# rc2014_16550c.net
KiCad netlist of a schematic drawn in EAGLE
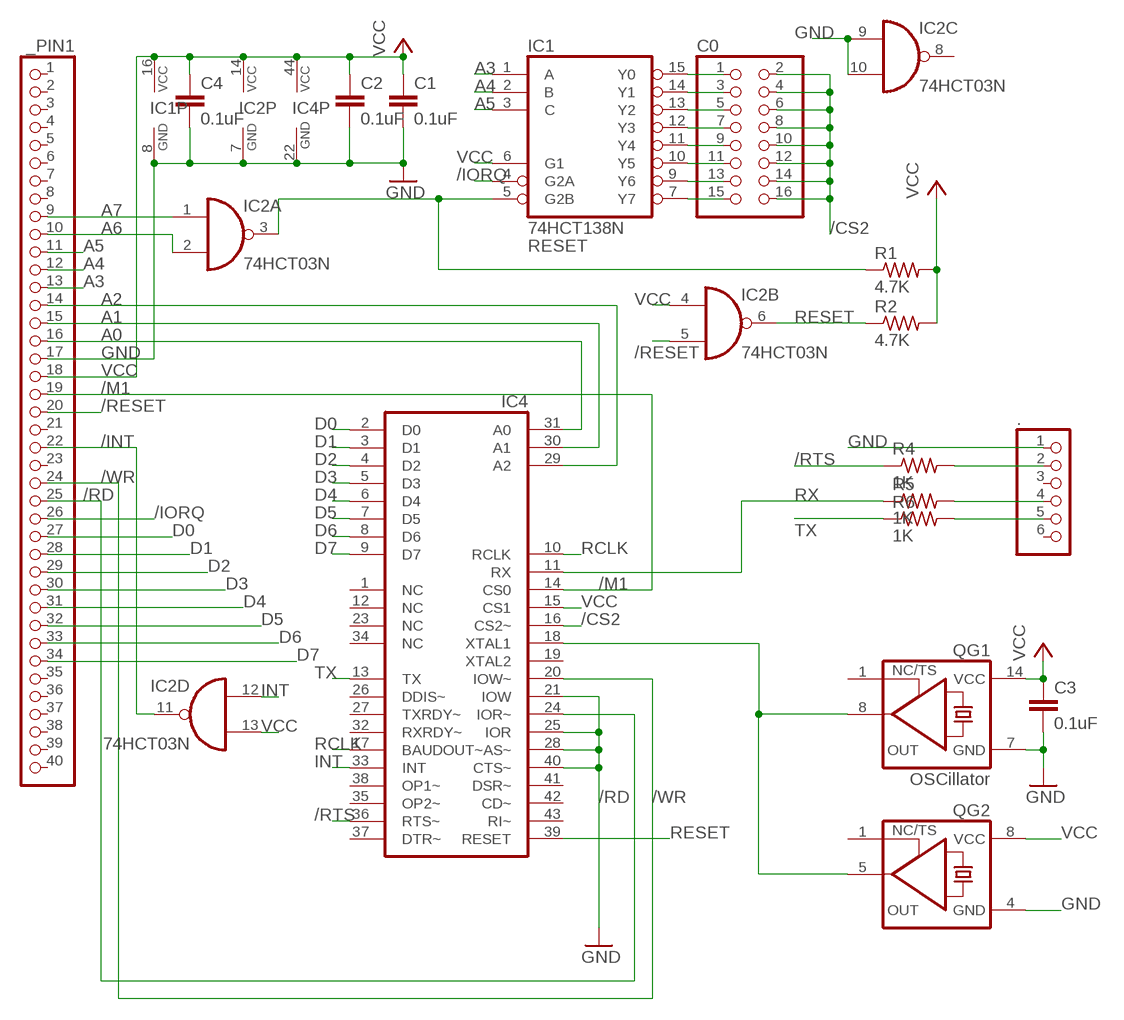
[diagram p0: schematic, sheet 1]

(export (version "E")
  (design (tool "Eeschema 10.0.6"))
  (components
    (comp (ref ".")
      (value "PINHD-1X6")
      (footprint "eagle-import:1X06")
      (libsource (lib "eagle-import") (part "PINHD-1X6"))
    )
    (comp (ref "C0")
      (value "PINHD-2X8")
      (footprint "eagle-import:2X08")
      (libsource (lib "eagle-import") (part "PINHD-2X8"))
    )
    (comp (ref "C1")
      (value "0.1uF")
      (footprint "eagle-import:C050-024X044")
      (libsource (lib "eagle-import") (part "C-EU050-024X044"))
    )
    (comp (ref "C2")
      (value "0.1uF")
      (footprint "eagle-import:C050-024X044")
      (libsource (lib "eagle-import") (part "C-EU050-024X044"))
    )
    (comp (ref "C3")
      (value "0.1uF")
      (footprint "eagle-import:C050-024X044")
      (libsource (lib "eagle-import") (part "C-EU050-024X044"))
    )
    (comp (ref "C4")
      (value "0.1uF")
      (footprint "eagle-import:C050-024X044")
      (libsource (lib "eagle-import") (part "C-EU050-024X044"))
    )
    (comp (ref "IC1")
      (value "74HCT138N")
      (footprint "eagle-import:DIL16")
      (libsource (lib "eagle-import") (part "74138NHCT"))
    )
    (comp (ref "IC2")
      (value "74HCT03N")
      (footprint "eagle-import:DIL14")
      (libsource (lib "eagle-import") (part "7400NHCT"))
    )
    (comp (ref "IC4")
      (value "XR-16C550JSOCKET44")
      (footprint "eagle-import:S44")
      (libsource (lib "eagle-import") (part "XR-16C550JSOCKET44"))
    )
    (comp (ref "QG1")
      (value "OSCillator")
      (footprint "eagle-import:DIL14S")
      (libsource (lib "eagle-import") (part "XO-14"))
    )
    (comp (ref "QG2")
      (value "XO-8")
      (footprint "eagle-import:DIL08S")
      (libsource (lib "eagle-import") (part "XO-8"))
    )
    (comp (ref "R1")
      (value "4.7K")
      (footprint "eagle-import:0207_10")
      (libsource (lib "eagle-import") (part "R-US_0207/10"))
    )
    (comp (ref "R2")
      (value "4.7K")
      (footprint "eagle-import:0207_10")
      (libsource (lib "eagle-import") (part "R-US_0207/10"))
    )
    (comp (ref "R4")
      (value "1K")
      (footprint "eagle-import:0207_10")
      (libsource (lib "eagle-import") (part "R-US_0207/10"))
    )
    (comp (ref "R5")
      (value "1K")
      (footprint "eagle-import:0207_10")
      (libsource (lib "eagle-import") (part "R-US_0207/10"))
    )
    (comp (ref "R6")
      (value "1K")
      (footprint "eagle-import:0207_10")
      (libsource (lib "eagle-import") (part "R-US_0207/10"))
    )
    (comp (ref "_PIN1")
      (value "PINHD-1X40")
      (footprint "eagle-import:1X40")
      (libsource (lib "eagle-import") (part "PINHD-1X40"))
    )
  )
  (nets
    (net (code "1") (name "/A0") (class "Default")
      (node (ref "IC4") (pin "31") (pinfunction "A0_31") (pintype "input"))
      (node (ref "_PIN1") (pin "16") (pinfunction "16_16") (pintype "passive"))
    )
    (net (code "2") (name "/A1") (class "Default")
      (node (ref "IC4") (pin "30") (pinfunction "A1_30") (pintype "input"))
      (node (ref "_PIN1") (pin "15") (pinfunction "15_15") (pintype "passive"))
    )
    (net (code "3") (name "/A2") (class "Default")
      (node (ref "IC4") (pin "29") (pinfunction "A2_29") (pintype "input"))
      (node (ref "_PIN1") (pin "14") (pinfunction "14_14") (pintype "passive"))
    )
    (net (code "4") (name "/A3") (class "Default")
      (node (ref "IC1") (pin "1") (pinfunction "A_1") (pintype "input"))
      (node (ref "_PIN1") (pin "13") (pinfunction "13_13") (pintype "passive"))
    )
    (net (code "5") (name "/A4") (class "Default")
      (node (ref "IC1") (pin "2") (pinfunction "B_2") (pintype "input"))
      (node (ref "_PIN1") (pin "12") (pinfunction "12_12") (pintype "passive"))
    )
    (net (code "6") (name "/A5") (class "Default")
      (node (ref "IC1") (pin "3") (pinfunction "C_3") (pintype "input"))
      (node (ref "_PIN1") (pin "11") (pinfunction "11_11") (pintype "passive"))
    )
    (net (code "7") (name "/A6") (class "Default")
      (node (ref "IC2") (pin "2") (pinfunction "I1_2") (pintype "input"))
      (node (ref "_PIN1") (pin "10") (pinfunction "10_10") (pintype "passive"))
    )
    (net (code "8") (name "/A7") (class "Default")
      (node (ref "IC2") (pin "1") (pinfunction "I0_1") (pintype "input"))
      (node (ref "_PIN1") (pin "9") (pinfunction "9_9") (pintype "passive"))
    )
    (net (code "9") (name "/D0") (class "Default")
      (node (ref "IC4") (pin "2") (pinfunction "D0_2") (pintype "bidirectional"))
      (node (ref "_PIN1") (pin "27") (pinfunction "27_27") (pintype "passive"))
    )
    (net (code "10") (name "/D1") (class "Default")
      (node (ref "IC4") (pin "3") (pinfunction "D1_3") (pintype "bidirectional"))
      (node (ref "_PIN1") (pin "28") (pinfunction "28_28") (pintype "passive"))
    )
    (net (code "11") (name "/D2") (class "Default")
      (node (ref "IC4") (pin "4") (pinfunction "D2_4") (pintype "bidirectional"))
      (node (ref "_PIN1") (pin "29") (pinfunction "29_29") (pintype "passive"))
    )
    (net (code "12") (name "/D3") (class "Default")
      (node (ref "IC4") (pin "5") (pinfunction "D3_5") (pintype "bidirectional"))
      (node (ref "_PIN1") (pin "30") (pinfunction "30_30") (pintype "passive"))
    )
    (net (code "13") (name "/D4") (class "Default")
      (node (ref "IC4") (pin "6") (pinfunction "D4_6") (pintype "bidirectional"))
      (node (ref "_PIN1") (pin "31") (pinfunction "31_31") (pintype "passive"))
    )
    (net (code "14") (name "/D5") (class "Default")
      (node (ref "IC4") (pin "7") (pinfunction "D5_7") (pintype "bidirectional"))
      (node (ref "_PIN1") (pin "32") (pinfunction "32_32") (pintype "passive"))
    )
    (net (code "15") (name "/D6") (class "Default")
      (node (ref "IC4") (pin "8") (pinfunction "D6_8") (pintype "bidirectional"))
      (node (ref "_PIN1") (pin "33") (pinfunction "33_33") (pintype "passive"))
    )
    (net (code "16") (name "/D7") (class "Default")
      (node (ref "IC4") (pin "9") (pinfunction "D7_9") (pintype "bidirectional"))
      (node (ref "_PIN1") (pin "34") (pinfunction "34_34") (pintype "passive"))
    )
    (net (code "17") (name "/INT") (class "Default")
      (node (ref "IC2") (pin "12") (pinfunction "I0_12") (pintype "input"))
      (node (ref "IC4") (pin "33") (pinfunction "INT_33") (pintype "output"))
    )
    (net (code "18") (name "/RCLK") (class "Default")
      (node (ref "IC4") (pin "10") (pinfunction "RCLK_10") (pintype "input"))
      (node (ref "IC4") (pin "17") (pinfunction "BAUDOUT~{}_17") (pintype "output"))
    )
    (net (code "19") (name "/RESET") (class "Default")
      (node (ref "IC2") (pin "6") (pinfunction "O_6") (pintype "output"))
      (node (ref "IC4") (pin "39") (pinfunction "RESET_39") (pintype "input"))
      (node (ref "R2") (pin "1") (pinfunction "1_1") (pintype "passive"))
    )
    (net (code "20") (name "/RX") (class "Default")
      (node (ref "IC4") (pin "11") (pinfunction "RX_11") (pintype "input"))
      (node (ref "R5") (pin "1") (pinfunction "1_1") (pintype "passive"))
    )
    (net (code "21") (name "/TX") (class "Default")
      (node (ref "IC4") (pin "13") (pinfunction "TX_13") (pintype "output"))
      (node (ref "R6") (pin "1") (pinfunction "1_1") (pintype "passive"))
    )
    (net (code "22") (name "/{slash}CS2") (class "Default")
      (node (ref "C0") (pin "10") (pinfunction "10_10") (pintype "passive"))
      (node (ref "C0") (pin "12") (pinfunction "12_12") (pintype "passive"))
      (node (ref "C0") (pin "14") (pinfunction "14_14") (pintype "passive"))
      (node (ref "C0") (pin "16") (pinfunction "16_16") (pintype "passive"))
      (node (ref "C0") (pin "2") (pinfunction "2_2") (pintype "passive"))
      (node (ref "C0") (pin "4") (pinfunction "4_4") (pintype "passive"))
      (node (ref "C0") (pin "6") (pinfunction "6_6") (pintype "passive"))
      (node (ref "C0") (pin "8") (pinfunction "8_8") (pintype "passive"))
      (node (ref "IC4") (pin "16") (pinfunction "CS2~{}_16") (pintype "input"))
    )
    (net (code "23") (name "/{slash}INT") (class "Default")
      (node (ref "IC2") (pin "11") (pinfunction "O_11") (pintype "output"))
      (node (ref "_PIN1") (pin "22") (pinfunction "22_22") (pintype "passive"))
    )
    (net (code "24") (name "/{slash}IORQ") (class "Default")
      (node (ref "IC1") (pin "4") (pinfunction "G2A_4") (pintype "input"))
      (node (ref "_PIN1") (pin "26") (pinfunction "26_26") (pintype "passive"))
    )
    (net (code "25") (name "/{slash}M1") (class "Default")
      (node (ref "IC4") (pin "14") (pinfunction "CS0_14") (pintype "input"))
      (node (ref "_PIN1") (pin "19") (pinfunction "19_19") (pintype "passive"))
    )
    (net (code "26") (name "/{slash}RD") (class "Default")
      (node (ref "IC4") (pin "24") (pinfunction "IOR~{}_24") (pintype "input"))
      (node (ref "_PIN1") (pin "25") (pinfunction "25_25") (pintype "passive"))
    )
    (net (code "27") (name "/{slash}RESET") (class "Default")
      (node (ref "IC2") (pin "5") (pinfunction "I1_5") (pintype "input"))
      (node (ref "_PIN1") (pin "20") (pinfunction "20_20") (pintype "passive"))
    )
    (net (code "28") (name "/{slash}RTS") (class "Default")
      (node (ref "IC4") (pin "36") (pinfunction "RTS~{}_36") (pintype "output"))
      (node (ref "R4") (pin "1") (pinfunction "1_1") (pintype "passive"))
    )
    (net (code "29") (name "/{slash}WR") (class "Default")
      (node (ref "IC4") (pin "20") (pinfunction "IOW~{}_20") (pintype "input"))
      (node (ref "_PIN1") (pin "24") (pinfunction "24_24") (pintype "passive"))
    )
    (net (code "30") (name "GND") (class "Default")
      (node (ref ".") (pin "1") (pinfunction "1_1") (pintype "passive"))
      (node (ref "C1") (pin "2") (pinfunction "2_2") (pintype "passive"))
      (node (ref "C2") (pin "2") (pinfunction "2_2") (pintype "passive"))
      (node (ref "C3") (pin "2") (pinfunction "2_2") (pintype "passive"))
      (node (ref "C4") (pin "2") (pinfunction "2_2") (pintype "passive"))
      (node (ref "IC1") (pin "8") (pinfunction "GND_8") (pintype "power_in"))
      (node (ref "IC2") (pin "10") (pinfunction "I1_10") (pintype "input"))
      (node (ref "IC2") (pin "7") (pinfunction "GND_7") (pintype "power_in"))
      (node (ref "IC2") (pin "9") (pinfunction "I0_9") (pintype "input"))
      (node (ref "IC4") (pin "21") (pinfunction "IOW_21") (pintype "input"))
      (node (ref "IC4") (pin "22") (pinfunction "GND_22") (pintype "power_in"))
      (node (ref "IC4") (pin "25") (pinfunction "IOR_25") (pintype "input"))
      (node (ref "IC4") (pin "28") (pinfunction "AS~{}_28") (pintype "input"))
      (node (ref "IC4") (pin "40") (pinfunction "CTS~{}_40") (pintype "input"))
      (node (ref "QG1") (pin "7") (pinfunction "GND_7") (pintype "power_in"))
      (node (ref "QG2") (pin "4") (pinfunction "GND_4") (pintype "power_in"))
      (node (ref "_PIN1") (pin "17") (pinfunction "17_17") (pintype "passive"))
    )
    (net (code "31") (name "Net-(.-Pad2)") (class "Default")
      (node (ref ".") (pin "2") (pinfunction "2_2") (pintype "passive"))
      (node (ref "R4") (pin "2") (pinfunction "2_2") (pintype "passive"))
    )
    (net (code "32") (name "Net-(.-Pad4)") (class "Default")
      (node (ref ".") (pin "4") (pinfunction "4_4") (pintype "passive"))
      (node (ref "R5") (pin "2") (pinfunction "2_2") (pintype "passive"))
    )
    (net (code "33") (name "Net-(.-Pad5)") (class "Default")
      (node (ref ".") (pin "5") (pinfunction "5_5") (pintype "passive"))
      (node (ref "R6") (pin "2") (pinfunction "2_2") (pintype "passive"))
    )
    (net (code "34") (name "Net-(IC1A-G2B)") (class "Default")
      (node (ref "IC1") (pin "5") (pinfunction "G2B_5") (pintype "input"))
      (node (ref "IC2") (pin "3") (pinfunction "O_3") (pintype "output"))
      (node (ref "R1") (pin "1") (pinfunction "1_1") (pintype "passive"))
    )
    (net (code "35") (name "Net-(IC1A-Y0)") (class "Default")
      (node (ref "C0") (pin "1") (pinfunction "1_1") (pintype "passive"))
      (node (ref "IC1") (pin "15") (pinfunction "Y0_15") (pintype "output"))
    )
    (net (code "36") (name "Net-(IC1A-Y1)") (class "Default")
      (node (ref "C0") (pin "3") (pinfunction "3_3") (pintype "passive"))
      (node (ref "IC1") (pin "14") (pinfunction "Y1_14") (pintype "output"))
    )
    (net (code "37") (name "Net-(IC1A-Y2)") (class "Default")
      (node (ref "C0") (pin "5") (pinfunction "5_5") (pintype "passive"))
      (node (ref "IC1") (pin "13") (pinfunction "Y2_13") (pintype "output"))
    )
    (net (code "38") (name "Net-(IC1A-Y3)") (class "Default")
      (node (ref "C0") (pin "7") (pinfunction "7_7") (pintype "passive"))
      (node (ref "IC1") (pin "12") (pinfunction "Y3_12") (pintype "output"))
    )
    (net (code "39") (name "Net-(IC1A-Y4)") (class "Default")
      (node (ref "C0") (pin "9") (pinfunction "9_9") (pintype "passive"))
      (node (ref "IC1") (pin "11") (pinfunction "Y4_11") (pintype "output"))
    )
    (net (code "40") (name "Net-(IC1A-Y5)") (class "Default")
      (node (ref "C0") (pin "11") (pinfunction "11_11") (pintype "passive"))
      (node (ref "IC1") (pin "10") (pinfunction "Y5_10") (pintype "output"))
    )
    (net (code "41") (name "Net-(IC1A-Y6)") (class "Default")
      (node (ref "C0") (pin "13") (pinfunction "13_13") (pintype "passive"))
      (node (ref "IC1") (pin "9") (pinfunction "Y6_9") (pintype "output"))
    )
    (net (code "42") (name "Net-(IC1A-Y7)") (class "Default")
      (node (ref "C0") (pin "15") (pinfunction "15_15") (pintype "passive"))
      (node (ref "IC1") (pin "7") (pinfunction "Y7_7") (pintype "output"))
    )
    (net (code "43") (name "Net-(IC4A-XTAL1)") (class "Default")
      (node (ref "IC4") (pin "18") (pinfunction "XTAL1_18") (pintype "input"))
      (node (ref "QG1") (pin "8") (pinfunction "OUT_8") (pintype "output"))
      (node (ref "QG2") (pin "5") (pinfunction "OUT_5") (pintype "output"))
    )
    (net (code "44") (name "VCC") (class "Default")
      (node (ref "C1") (pin "1") (pinfunction "1_1") (pintype "passive"))
      (node (ref "C2") (pin "1") (pinfunction "1_1") (pintype "passive"))
      (node (ref "C3") (pin "1") (pinfunction "1_1") (pintype "passive"))
      (node (ref "C4") (pin "1") (pinfunction "1_1") (pintype "passive"))
      (node (ref "IC1") (pin "16") (pinfunction "VCC_16") (pintype "power_in"))
      (node (ref "IC1") (pin "6") (pinfunction "G1_6") (pintype "input"))
      (node (ref "IC2") (pin "13") (pinfunction "I1_13") (pintype "input"))
      (node (ref "IC2") (pin "14") (pinfunction "VCC_14") (pintype "power_in"))
      (node (ref "IC2") (pin "4") (pinfunction "I0_4") (pintype "input"))
      (node (ref "IC4") (pin "15") (pinfunction "CS1_15") (pintype "input"))
      (node (ref "IC4") (pin "44") (pinfunction "VCC_44") (pintype "power_in"))
      (node (ref "QG1") (pin "14") (pinfunction "VCC_14") (pintype "power_in"))
      (node (ref "QG2") (pin "8") (pinfunction "VCC_8") (pintype "power_in"))
      (node (ref "R1") (pin "2") (pinfunction "2_2") (pintype "passive"))
      (node (ref "R2") (pin "2") (pinfunction "2_2") (pintype "passive"))
      (node (ref "_PIN1") (pin "18") (pinfunction "18_18") (pintype "passive"))
    )
    (net (code "45") (name "unconnected-(.-Pad3)") (class "Default")
      (node (ref ".") (pin "3") (pinfunction "3_3") (pintype "passive"))
    )
    (net (code "46") (name "unconnected-(.-Pad6)") (class "Default")
      (node (ref ".") (pin "6") (pinfunction "6_6") (pintype "passive"))
    )
    (net (code "47") (name "unconnected-(IC2C-O-Pad8)") (class "Default")
      (node (ref "IC2") (pin "8") (pinfunction "O_8") (pintype "output"))
    )
    (net (code "48") (name "unconnected-(IC4A-CD~{}-Pad42)") (class "Default")
      (node (ref "IC4") (pin "42") (pinfunction "CD~{}_42") (pintype "input"))
    )
    (net (code "49") (name "unconnected-(IC4A-DDIS~{}-Pad26)") (class "Default")
      (node (ref "IC4") (pin "26") (pinfunction "DDIS~{}_26") (pintype "output"))
    )
    (net (code "50") (name "unconnected-(IC4A-DSR~{}-Pad41)") (class "Default")
      (node (ref "IC4") (pin "41") (pinfunction "DSR~{}_41") (pintype "input"))
    )
    (net (code "51") (name "unconnected-(IC4A-DTR~{}-Pad37)") (class "Default")
      (node (ref "IC4") (pin "37") (pinfunction "DTR~{}_37") (pintype "output"))
    )
    (net (code "52") (name "unconnected-(IC4A-NC-Pad1)") (class "Default")
      (node (ref "IC4") (pin "1") (pinfunction "NC_1") (pintype "no_connect"))
    )
    (net (code "53") (name "unconnected-(IC4A-NC-Pad12)") (class "Default")
      (node (ref "IC4") (pin "12") (pinfunction "NC_12") (pintype "no_connect"))
    )
    (net (code "54") (name "unconnected-(IC4A-NC-Pad23)") (class "Default")
      (node (ref "IC4") (pin "23") (pinfunction "NC_23") (pintype "no_connect"))
    )
    (net (code "55") (name "unconnected-(IC4A-NC-Pad34)") (class "Default")
      (node (ref "IC4") (pin "34") (pinfunction "NC_34") (pintype "no_connect"))
    )
    (net (code "56") (name "unconnected-(IC4A-OP1~{}-Pad38)") (class "Default")
      (node (ref "IC4") (pin "38") (pinfunction "OP1~{}_38") (pintype "output"))
    )
    (net (code "57") (name "unconnected-(IC4A-OP2~{}-Pad35)") (class "Default")
      (node (ref "IC4") (pin "35") (pinfunction "OP2~{}_35") (pintype "output"))
    )
    (net (code "58") (name "unconnected-(IC4A-RI~{}-Pad43)") (class "Default")
      (node (ref "IC4") (pin "43") (pinfunction "RI~{}_43") (pintype "input"))
    )
    (net (code "59") (name "unconnected-(IC4A-RXRDY~{}-Pad32)") (class "Default")
      (node (ref "IC4") (pin "32") (pinfunction "RXRDY~{}_32") (pintype "output"))
    )
    (net (code "60") (name "unconnected-(IC4A-TXRDY~{}-Pad27)") (class "Default")
      (node (ref "IC4") (pin "27") (pinfunction "TXRDY~{}_27") (pintype "output"))
    )
    (net (code "61") (name "unconnected-(IC4A-XTAL2-Pad19)") (class "Default")
      (node (ref "IC4") (pin "19") (pinfunction "XTAL2_19") (pintype "input"))
    )
    (net (code "62") (name "unconnected-(QG1-TS-Pad1)") (class "Default")
      (node (ref "QG1") (pin "1") (pinfunction "TS_1") (pintype "passive"))
    )
    (net (code "63") (name "unconnected-(QG2-TS-Pad1)") (class "Default")
      (node (ref "QG2") (pin "1") (pinfunction "TS_1") (pintype "passive"))
    )
    (net (code "64") (name "unconnected-(_PIN1-Pad1)") (class "Default")
      (node (ref "_PIN1") (pin "1") (pinfunction "1_1") (pintype "passive"))
    )
    (net (code "65") (name "unconnected-(_PIN1-Pad2)") (class "Default")
      (node (ref "_PIN1") (pin "2") (pinfunction "2_2") (pintype "passive"))
    )
    (net (code "66") (name "unconnected-(_PIN1-Pad3)") (class "Default")
      (node (ref "_PIN1") (pin "3") (pinfunction "3_3") (pintype "passive"))
    )
    (net (code "67") (name "unconnected-(_PIN1-Pad4)") (class "Default")
      (node (ref "_PIN1") (pin "4") (pinfunction "4_4") (pintype "passive"))
    )
    (net (code "68") (name "unconnected-(_PIN1-Pad5)") (class "Default")
      (node (ref "_PIN1") (pin "5") (pinfunction "5_5") (pintype "passive"))
    )
    (net (code "69") (name "unconnected-(_PIN1-Pad6)") (class "Default")
      (node (ref "_PIN1") (pin "6") (pinfunction "6_6") (pintype "passive"))
    )
    (net (code "70") (name "unconnected-(_PIN1-Pad7)") (class "Default")
      (node (ref "_PIN1") (pin "7") (pinfunction "7_7") (pintype "passive"))
    )
    (net (code "71") (name "unconnected-(_PIN1-Pad8)") (class "Default")
      (node (ref "_PIN1") (pin "8") (pinfunction "8_8") (pintype "passive"))
    )
    (net (code "72") (name "unconnected-(_PIN1-Pad21)") (class "Default")
      (node (ref "_PIN1") (pin "21") (pinfunction "21_21") (pintype "passive"))
    )
    (net (code "73") (name "unconnected-(_PIN1-Pad23)") (class "Default")
      (node (ref "_PIN1") (pin "23") (pinfunction "23_23") (pintype "passive"))
    )
    (net (code "74") (name "unconnected-(_PIN1-Pad35)") (class "Default")
      (node (ref "_PIN1") (pin "35") (pinfunction "35_35") (pintype "passive"))
    )
    (net (code "75") (name "unconnected-(_PIN1-Pad36)") (class "Default")
      (node (ref "_PIN1") (pin "36") (pinfunction "36_36") (pintype "passive"))
    )
    (net (code "76") (name "unconnected-(_PIN1-Pad37)") (class "Default")
      (node (ref "_PIN1") (pin "37") (pinfunction "37_37") (pintype "passive"))
    )
    (net (code "77") (name "unconnected-(_PIN1-Pad38)") (class "Default")
      (node (ref "_PIN1") (pin "38") (pinfunction "38_38") (pintype "passive"))
    )
    (net (code "78") (name "unconnected-(_PIN1-Pad39)") (class "Default")
      (node (ref "_PIN1") (pin "39") (pinfunction "39_39") (pintype "passive"))
    )
    (net (code "79") (name "unconnected-(_PIN1-Pad40)") (class "Default")
      (node (ref "_PIN1") (pin "40") (pinfunction "40_40") (pintype "passive"))
    )
  )
)
